# 5_cyber60-smk_periferals.net
KiCad netlist of a schematic drawn in Altium Designer
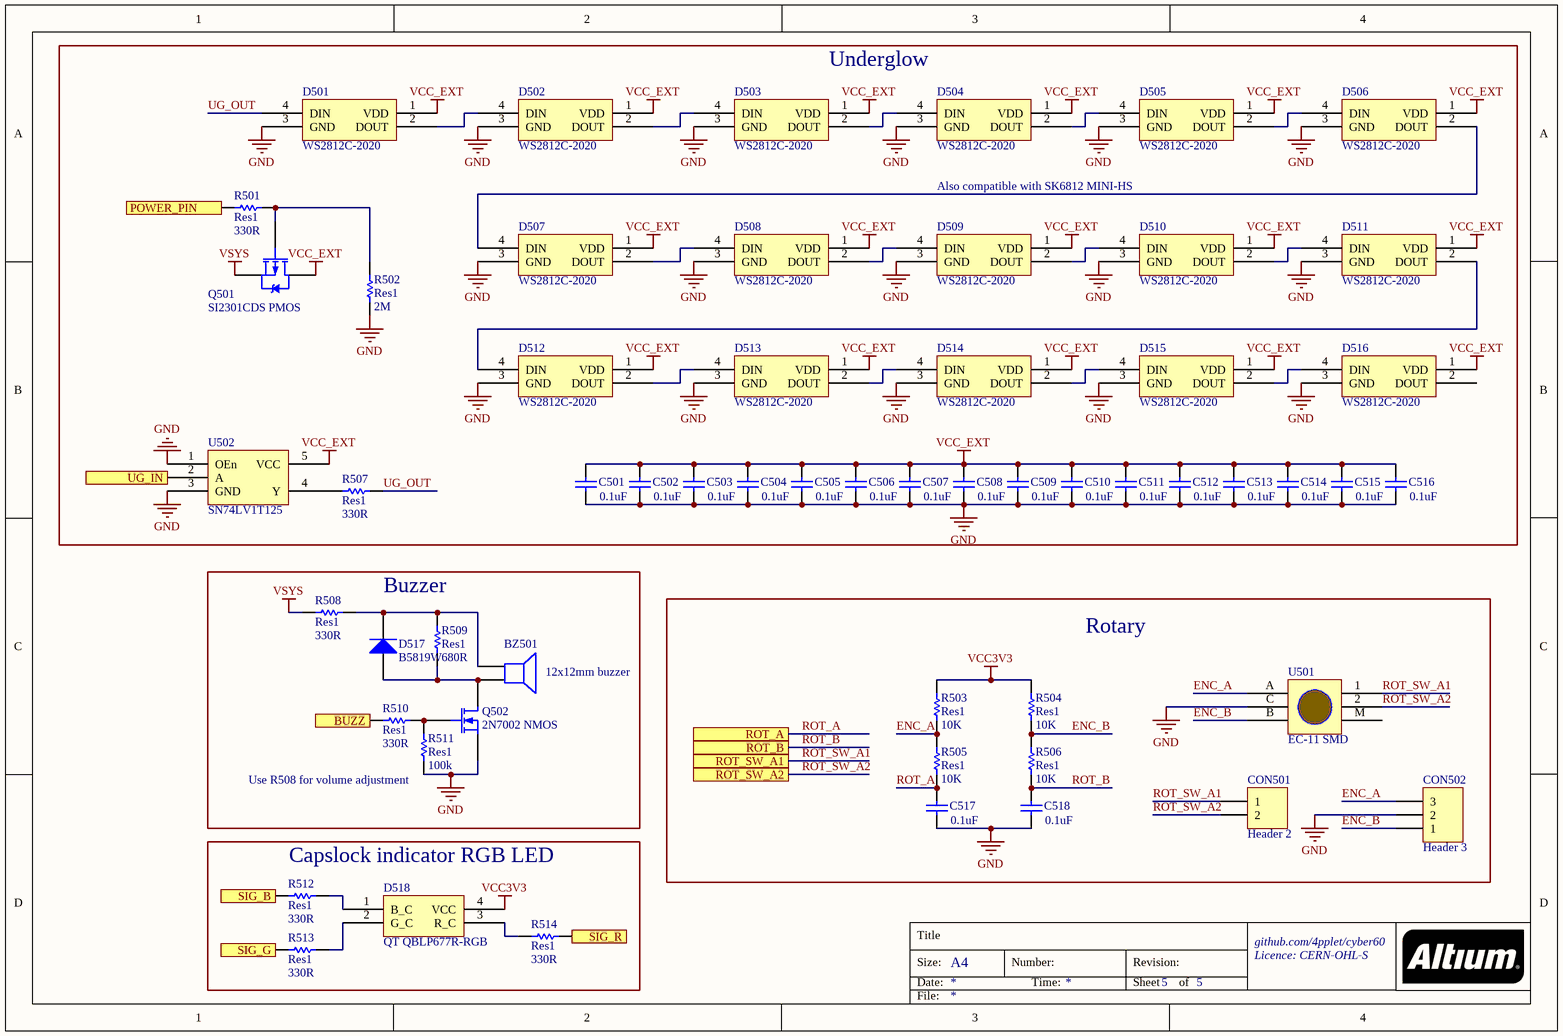
[diagram p0: 5_cyber60-smk_periferals.SchDoc]

(export (version "E")
  (design (tool "Eeschema 10.0.6"))
  (components
    (comp (ref "BZ501")
      (value "12x12mm buzzer")
      (footprint "buzzer 12x12")
      (description "Loudspeaker")
      (fields (field (name "LCSC PART #") "C409829") (field (name "MRF.PART") "YS-SBZ1230"))
      (libsource (lib "Miscellaneous Devices") (part "Speaker"))
    )
    (comp (ref "C501")
      (value "0.1uF")
      (footprint "C0603[1608]")
      (description "Capacitor")
      (fields (field (name "MFG") "KEMET") (field (name "LCSC PART #") "C14663"))
      (libsource (lib "Miscellaneous Devices") (part "Cap"))
    )
    (comp (ref "C502")
      (value "0.1uF")
      (footprint "C0603[1608]")
      (description "Capacitor")
      (fields (field (name "MFG") "KEMET") (field (name "LCSC PART #") "C14663"))
      (libsource (lib "Miscellaneous Devices") (part "Cap"))
    )
    (comp (ref "C503")
      (value "0.1uF")
      (footprint "C0603[1608]")
      (description "Capacitor")
      (fields (field (name "MFG") "KEMET") (field (name "LCSC PART #") "C14663"))
      (libsource (lib "Miscellaneous Devices") (part "Cap"))
    )
    (comp (ref "C504")
      (value "0.1uF")
      (footprint "C0603[1608]")
      (description "Capacitor")
      (fields (field (name "MFG") "KEMET") (field (name "LCSC PART #") "C14663"))
      (libsource (lib "Miscellaneous Devices") (part "Cap"))
    )
    (comp (ref "C505")
      (value "0.1uF")
      (footprint "C0603[1608]")
      (description "Capacitor")
      (fields (field (name "MFG") "KEMET") (field (name "LCSC PART #") "C14663"))
      (libsource (lib "Miscellaneous Devices") (part "Cap"))
    )
    (comp (ref "C506")
      (value "0.1uF")
      (footprint "C0603[1608]")
      (description "Capacitor")
      (fields (field (name "MFG") "KEMET") (field (name "LCSC PART #") "C14663"))
      (libsource (lib "Miscellaneous Devices") (part "Cap"))
    )
    (comp (ref "C507")
      (value "0.1uF")
      (footprint "C0603[1608]")
      (description "Capacitor")
      (fields (field (name "MFG") "KEMET") (field (name "LCSC PART #") "C14663"))
      (libsource (lib "Miscellaneous Devices") (part "Cap"))
    )
    (comp (ref "C508")
      (value "0.1uF")
      (footprint "C0603[1608]")
      (description "Capacitor")
      (fields (field (name "MFG") "KEMET") (field (name "LCSC PART #") "C14663"))
      (libsource (lib "Miscellaneous Devices") (part "Cap"))
    )
    (comp (ref "C509")
      (value "0.1uF")
      (footprint "C0603[1608]")
      (description "Capacitor")
      (fields (field (name "MFG") "KEMET") (field (name "LCSC PART #") "C14663"))
      (libsource (lib "Miscellaneous Devices") (part "Cap"))
    )
    (comp (ref "C510")
      (value "0.1uF")
      (footprint "C0603[1608]")
      (description "Capacitor")
      (fields (field (name "MFG") "KEMET") (field (name "LCSC PART #") "C14663"))
      (libsource (lib "Miscellaneous Devices") (part "Cap"))
    )
    (comp (ref "C511")
      (value "0.1uF")
      (footprint "C0603[1608]")
      (description "Capacitor")
      (fields (field (name "MFG") "KEMET") (field (name "LCSC PART #") "C14663"))
      (libsource (lib "Miscellaneous Devices") (part "Cap"))
    )
    (comp (ref "C512")
      (value "0.1uF")
      (footprint "C0603[1608]")
      (description "Capacitor")
      (fields (field (name "MFG") "KEMET") (field (name "LCSC PART #") "C14663"))
      (libsource (lib "Miscellaneous Devices") (part "Cap"))
    )
    (comp (ref "C513")
      (value "0.1uF")
      (footprint "C0603[1608]")
      (description "Capacitor")
      (fields (field (name "MFG") "KEMET") (field (name "LCSC PART #") "C14663"))
      (libsource (lib "Miscellaneous Devices") (part "Cap"))
    )
    (comp (ref "C514")
      (value "0.1uF")
      (footprint "C0603[1608]")
      (description "Capacitor")
      (fields (field (name "MFG") "KEMET") (field (name "LCSC PART #") "C14663"))
      (libsource (lib "Miscellaneous Devices") (part "Cap"))
    )
    (comp (ref "C515")
      (value "0.1uF")
      (footprint "C0603[1608]")
      (description "Capacitor")
      (fields (field (name "MFG") "KEMET") (field (name "LCSC PART #") "C14663"))
      (libsource (lib "Miscellaneous Devices") (part "Cap"))
    )
    (comp (ref "C516")
      (value "0.1uF")
      (footprint "C0603[1608]")
      (description "Capacitor")
      (fields (field (name "MFG") "KEMET") (field (name "LCSC PART #") "C14663"))
      (libsource (lib "Miscellaneous Devices") (part "Cap"))
    )
    (comp (ref "C517")
      (value "0.1uF")
      (footprint "C0603[1608]")
      (description "Capacitor")
      (fields (field (name "MFG") "KEMET") (field (name "LCSC PART #") "C14663"))
      (libsource (lib "Miscellaneous Devices") (part "Cap"))
    )
    (comp (ref "C518")
      (value "0.1uF")
      (footprint "C0603[1608]")
      (description "Capacitor")
      (fields (field (name "MFG") "KEMET") (field (name "LCSC PART #") "C14663"))
      (libsource (lib "Miscellaneous Devices") (part "Cap"))
    )
    (comp (ref "CON501")
      (value "Header 2")
      (footprint "HDR1X2")
      (description "Header, 2-Pin")
      (libsource (lib "Miscellaneous Connectors") (part "Header 2"))
    )
    (comp (ref "CON502")
      (value "Header 3")
      (footprint "HDR1X3")
      (description "Header, 3-Pin")
      (libsource (lib "Miscellaneous Connectors") (part "Header 3"))
    )
    (comp (ref "D501")
      (value "WS2812C-2020")
      (footprint "WS2812B - 2020")
      (fields (field (name "LCSC PART #") "C965556"))
      (libsource (lib "Keebs") (part "WS2812B"))
    )
    (comp (ref "D502")
      (value "WS2812C-2020")
      (footprint "WS2812B - 2020")
      (fields (field (name "LCSC PART #") "C965556"))
      (libsource (lib "Keebs") (part "WS2812B"))
    )
    (comp (ref "D503")
      (value "WS2812C-2020")
      (footprint "WS2812B - 2020")
      (fields (field (name "LCSC PART #") "C965556"))
      (libsource (lib "Keebs") (part "WS2812B"))
    )
    (comp (ref "D504")
      (value "WS2812C-2020")
      (footprint "WS2812B - 2020")
      (fields (field (name "LCSC PART #") "C965556"))
      (libsource (lib "Keebs") (part "WS2812B"))
    )
    (comp (ref "D505")
      (value "WS2812C-2020")
      (footprint "WS2812B - 2020")
      (fields (field (name "LCSC PART #") "C965556"))
      (libsource (lib "Keebs") (part "WS2812B"))
    )
    (comp (ref "D506")
      (value "WS2812C-2020")
      (footprint "WS2812B - 2020")
      (fields (field (name "LCSC PART #") "C965556"))
      (libsource (lib "Keebs") (part "WS2812B"))
    )
    (comp (ref "D507")
      (value "WS2812C-2020")
      (footprint "WS2812B - 2020")
      (fields (field (name "LCSC PART #") "C965556"))
      (libsource (lib "Keebs") (part "WS2812B"))
    )
    (comp (ref "D508")
      (value "WS2812C-2020")
      (footprint "WS2812B - 2020")
      (fields (field (name "LCSC PART #") "C965556"))
      (libsource (lib "Keebs") (part "WS2812B"))
    )
    (comp (ref "D509")
      (value "WS2812C-2020")
      (footprint "WS2812B - 2020")
      (fields (field (name "LCSC PART #") "C965556"))
      (libsource (lib "Keebs") (part "WS2812B"))
    )
    (comp (ref "D510")
      (value "WS2812C-2020")
      (footprint "WS2812B - 2020")
      (fields (field (name "LCSC PART #") "C965556"))
      (libsource (lib "Keebs") (part "WS2812B"))
    )
    (comp (ref "D511")
      (value "WS2812C-2020")
      (footprint "WS2812B - 2020")
      (fields (field (name "LCSC PART #") "C965556"))
      (libsource (lib "Keebs") (part "WS2812B"))
    )
    (comp (ref "D512")
      (value "WS2812C-2020")
      (footprint "WS2812B - 2020")
      (fields (field (name "LCSC PART #") "C965556"))
      (libsource (lib "Keebs") (part "WS2812B"))
    )
    (comp (ref "D513")
      (value "WS2812C-2020")
      (footprint "WS2812B - 2020")
      (fields (field (name "LCSC PART #") "C965556"))
      (libsource (lib "Keebs") (part "WS2812B"))
    )
    (comp (ref "D514")
      (value "WS2812C-2020")
      (footprint "WS2812B - 2020")
      (fields (field (name "LCSC PART #") "C965556"))
      (libsource (lib "Keebs") (part "WS2812B"))
    )
    (comp (ref "D515")
      (value "WS2812C-2020")
      (footprint "WS2812B - 2020")
      (fields (field (name "LCSC PART #") "C965556"))
      (libsource (lib "Keebs") (part "WS2812B"))
    )
    (comp (ref "D516")
      (value "WS2812C-2020")
      (footprint "WS2812B - 2020")
      (fields (field (name "LCSC PART #") "C965556"))
      (libsource (lib "Keebs") (part "WS2812B"))
    )
    (comp (ref "D517")
      (value "B5819W")
      (footprint "SOD-123")
      (description "Default Diode")
      (fields (field (name "LCSC PART #") "C8598"))
      (libsource (lib "Miscellaneous Devices") (part "Diode"))
    )
    (comp (ref "D518")
      (value "QT QBLP677R-RGB")
      (footprint "QT QBLP677R-RGB")
      (description "RGB LED")
      (fields (field (name "MFG") "QT Brightek (QTB)"))
      (libsource (lib "Keebs") (part "QT QBLP677R-RGB"))
    )
    (comp (ref "Q501")
      (value "SI2301CDS PMOS")
      (footprint "SOT-23-3")
      (description "P-Channel Power MOSFET")
      (fields (field (name "MRF.PART") "SI2301CDS-T1-GE3") (field (name "LCSC PART #") "C10487"))
      (libsource (lib "Miscellaneous Devices") (part "PMOS-2"))
    )
    (comp (ref "Q502")
      (value "2N7002 NMOS")
      (footprint "SOT-23-3")
      (description "N-Channel MOSFET")
      (fields (field (name "LCSC PART #") "C8545") (field (name "MRF.PART") "2N7002"))
      (libsource (lib "Miscellaneous Devices") (part "MOSFET-N"))
    )
    (comp (ref "R501")
      (value "Res1")
      (footprint "R0603[1608]")
      (description "Resistor")
      (fields
        (field (name "ALTIUM_VALUE") "330R")
        (field (name "LCSC PART #") "C23138")
        (field (name "MRF.PART") "0603WAF3300T5E")
      )
      (libsource (lib "Miscellaneous Devices") (part "Res1"))
    )
    (comp (ref "R502")
      (value "Res1")
      (footprint "R0603[1608]")
      (description "Resistor")
      (fields
        (field (name "ALTIUM_VALUE") "2M")
        (field (name "MRF.PART") "0603WAF2004T5E")
        (field (name "LCSC PART #") "C22976")
      )
      (libsource (lib "Miscellaneous Devices") (part "Res1"))
    )
    (comp (ref "R503")
      (value "Res1")
      (footprint "R0603[1608]")
      (description "Resistor")
      (fields
        (field (name "ALTIUM_VALUE") "10K")
        (field (name "MRF.PART") "0603WAF1002T5E")
        (field (name "LCSC PART #") "C25804")
      )
      (libsource (lib "Miscellaneous Devices") (part "Res1"))
    )
    (comp (ref "R504")
      (value "Res1")
      (footprint "R0603[1608]")
      (description "Resistor")
      (fields
        (field (name "ALTIUM_VALUE") "10K")
        (field (name "MRF.PART") "0603WAF1002T5E")
        (field (name "LCSC PART #") "C25804")
      )
      (libsource (lib "Miscellaneous Devices") (part "Res1"))
    )
    (comp (ref "R505")
      (value "Res1")
      (footprint "R0603[1608]")
      (description "Resistor")
      (fields
        (field (name "ALTIUM_VALUE") "10K")
        (field (name "MRF.PART") "0603WAF1002T5E")
        (field (name "LCSC PART #") "C25804")
      )
      (libsource (lib "Miscellaneous Devices") (part "Res1"))
    )
    (comp (ref "R506")
      (value "Res1")
      (footprint "R0603[1608]")
      (description "Resistor")
      (fields
        (field (name "ALTIUM_VALUE") "10K")
        (field (name "MRF.PART") "0603WAF1002T5E")
        (field (name "LCSC PART #") "C25804")
      )
      (libsource (lib "Miscellaneous Devices") (part "Res1"))
    )
    (comp (ref "R507")
      (value "Res1")
      (footprint "R0603[1608]")
      (description "Resistor")
      (fields
        (field (name "ALTIUM_VALUE") "330R")
        (field (name "LCSC PART #") "C23138")
        (field (name "MRF.PART") "0603WAF3300T5E")
      )
      (libsource (lib "Miscellaneous Devices") (part "Res1"))
    )
    (comp (ref "R508")
      (value "Res1")
      (footprint "R0603[1608]")
      (description "Resistor")
      (fields
        (field (name "ALTIUM_VALUE") "330R")
        (field (name "LCSC PART #") "C23138")
        (field (name "MRF.PART") "0603WAF3300T5E")
      )
      (libsource (lib "Miscellaneous Devices") (part "Res1"))
    )
    (comp (ref "R509")
      (value "Res1")
      (footprint "R0603[1608]")
      (description "Resistor")
      (fields
        (field (name "ALTIUM_VALUE") "680R")
        (field (name "MRF.PART") "0603WAF6800T5E")
        (field (name "LCSC PART #") "C23228")
      )
      (libsource (lib "Miscellaneous Devices") (part "Res1"))
    )
    (comp (ref "R510")
      (value "Res1")
      (footprint "R0603[1608]")
      (description "Resistor")
      (fields
        (field (name "ALTIUM_VALUE") "330R")
        (field (name "LCSC PART #") "C23138")
        (field (name "MRF.PART") "0603WAF3300T5E")
      )
      (libsource (lib "Miscellaneous Devices") (part "Res1"))
    )
    (comp (ref "R511")
      (value "Res1")
      (footprint "R0603[1608]")
      (description "Resistor")
      (fields
        (field (name "ALTIUM_VALUE") "100k")
        (field (name "MRF.PART") "0603WAF1003T5E")
        (field (name "LCSC PART #") "C25803")
      )
      (libsource (lib "Miscellaneous Devices") (part "Res1"))
    )
    (comp (ref "R512")
      (value "Res1")
      (footprint "R0603[1608]")
      (description "Resistor")
      (fields
        (field (name "ALTIUM_VALUE") "330R")
        (field (name "LCSC PART #") "C23138")
        (field (name "MRF.PART") "0603WAF3300T5E")
      )
      (libsource (lib "Miscellaneous Devices") (part "Res1"))
    )
    (comp (ref "R513")
      (value "Res1")
      (footprint "R0603[1608]")
      (description "Resistor")
      (fields
        (field (name "ALTIUM_VALUE") "330R")
        (field (name "LCSC PART #") "C23138")
        (field (name "MRF.PART") "0603WAF3300T5E")
      )
      (libsource (lib "Miscellaneous Devices") (part "Res1"))
    )
    (comp (ref "R514")
      (value "Res1")
      (footprint "R0603[1608]")
      (description "Resistor")
      (fields
        (field (name "ALTIUM_VALUE") "330R")
        (field (name "LCSC PART #") "C23138")
        (field (name "MRF.PART") "0603WAF3300T5E")
      )
      (libsource (lib "Miscellaneous Devices") (part "Res1"))
    )
    (comp (ref "U501") (value "EC-11 SMD") (footprint "EC11-SMD") (libsource (lib "Keebs") (part "EC-11")))
    (comp (ref "U502")
      (value "SN74LV1T125")
      (footprint "SOT-23-5")
      (description "SN74LV1T125 or SN74LV1T34. Connect OE to GND")
      (fields (field (name "LCSC PART #") "C473338") (field (name "MRF.PART") "SN74LV1T125DBVR"))
      (libsource (lib "Keebs") (part "SN74LV1T125"))
    )
  )
  (nets
    (net (code "1") (name "/BUZZ") (class "Default")
      (node (ref "R510") (pin "2") (pinfunction "2_2") (pintype "passive"))
    )
    (net (code "2") (name "/ENC_A") (class "Default")
      (node (ref "CON502") (pin "3") (pinfunction "3_3") (pintype "passive"))
      (node (ref "R503") (pin "2") (pinfunction "2_2") (pintype "passive"))
      (node (ref "R505") (pin "1") (pinfunction "1_1") (pintype "passive"))
      (node (ref "U501") (pin "A") (pinfunction "B_A") (pintype "passive"))
    )
    (net (code "3") (name "/ENC_B") (class "Default")
      (node (ref "CON502") (pin "1") (pinfunction "1_1") (pintype "passive"))
      (node (ref "R504") (pin "2") (pinfunction "2_2") (pintype "passive"))
      (node (ref "R506") (pin "1") (pinfunction "1_1") (pintype "passive"))
      (node (ref "U501") (pin "B") (pinfunction "B_B") (pintype "passive"))
    )
    (net (code "4") (name "/POWER_PIN") (class "Default")
      (node (ref "R501") (pin "1") (pinfunction "1_1") (pintype "passive"))
    )
    (net (code "5") (name "/ROT_A") (class "Default")
      (node (ref "C517") (pin "2") (pinfunction "2_2") (pintype "passive"))
      (node (ref "R505") (pin "2") (pinfunction "2_2") (pintype "passive"))
    )
    (net (code "6") (name "/ROT_B") (class "Default")
      (node (ref "C518") (pin "2") (pinfunction "2_2") (pintype "passive"))
      (node (ref "R506") (pin "2") (pinfunction "2_2") (pintype "passive"))
    )
    (net (code "7") (name "/ROT_SW_A1") (class "Default")
      (node (ref "CON501") (pin "1") (pinfunction "1_1") (pintype "passive"))
      (node (ref "U501") (pin "1") (pinfunction "1_1") (pintype "passive"))
    )
    (net (code "8") (name "/ROT_SW_A2") (class "Default")
      (node (ref "CON501") (pin "2") (pinfunction "2_2") (pintype "passive"))
      (node (ref "U501") (pin "2") (pinfunction "2_2") (pintype "passive"))
    )
    (net (code "9") (name "/SIG_B") (class "Default")
      (node (ref "R512") (pin "2") (pinfunction "2_2") (pintype "passive"))
    )
    (net (code "10") (name "/SIG_G") (class "Default")
      (node (ref "R513") (pin "2") (pinfunction "2_2") (pintype "passive"))
    )
    (net (code "11") (name "/SIG_R") (class "Default")
      (node (ref "R514") (pin "1") (pinfunction "1_1") (pintype "passive"))
    )
    (net (code "12") (name "/UG_IN") (class "Default")
      (node (ref "U502") (pin "2") (pinfunction "A_2") (pintype "passive"))
    )
    (net (code "13") (name "/UG_OUT") (class "Default")
      (node (ref "D501") (pin "4") (pinfunction "DIN_4") (pintype "passive"))
      (node (ref "R507") (pin "1") (pinfunction "1_1") (pintype "passive"))
    )
    (net (code "14") (name "GND") (class "Default")
      (node (ref "C501") (pin "1") (pinfunction "1_1") (pintype "passive"))
      (node (ref "C502") (pin "1") (pinfunction "1_1") (pintype "passive"))
      (node (ref "C503") (pin "1") (pinfunction "1_1") (pintype "passive"))
      (node (ref "C504") (pin "1") (pinfunction "1_1") (pintype "passive"))
      (node (ref "C505") (pin "1") (pinfunction "1_1") (pintype "passive"))
      (node (ref "C506") (pin "1") (pinfunction "1_1") (pintype "passive"))
      (node (ref "C507") (pin "1") (pinfunction "1_1") (pintype "passive"))
      (node (ref "C508") (pin "1") (pinfunction "1_1") (pintype "passive"))
      (node (ref "C509") (pin "1") (pinfunction "1_1") (pintype "passive"))
      (node (ref "C510") (pin "1") (pinfunction "1_1") (pintype "passive"))
      (node (ref "C511") (pin "1") (pinfunction "1_1") (pintype "passive"))
      (node (ref "C512") (pin "1") (pinfunction "1_1") (pintype "passive"))
      (node (ref "C513") (pin "1") (pinfunction "1_1") (pintype "passive"))
      (node (ref "C514") (pin "1") (pinfunction "1_1") (pintype "passive"))
      (node (ref "C515") (pin "1") (pinfunction "1_1") (pintype "passive"))
      (node (ref "C516") (pin "1") (pinfunction "1_1") (pintype "passive"))
      (node (ref "C517") (pin "1") (pinfunction "1_1") (pintype "passive"))
      (node (ref "C518") (pin "1") (pinfunction "1_1") (pintype "passive"))
      (node (ref "CON502") (pin "2") (pinfunction "2_2") (pintype "passive"))
      (node (ref "D501") (pin "3") (pinfunction "GND_3") (pintype "passive"))
      (node (ref "D502") (pin "3") (pinfunction "GND_3") (pintype "passive"))
      (node (ref "D503") (pin "3") (pinfunction "GND_3") (pintype "passive"))
      (node (ref "D504") (pin "3") (pinfunction "GND_3") (pintype "passive"))
      (node (ref "D505") (pin "3") (pinfunction "GND_3") (pintype "passive"))
      (node (ref "D506") (pin "3") (pinfunction "GND_3") (pintype "passive"))
      (node (ref "D507") (pin "3") (pinfunction "GND_3") (pintype "passive"))
      (node (ref "D508") (pin "3") (pinfunction "GND_3") (pintype "passive"))
      (node (ref "D509") (pin "3") (pinfunction "GND_3") (pintype "passive"))
      (node (ref "D510") (pin "3") (pinfunction "GND_3") (pintype "passive"))
      (node (ref "D511") (pin "3") (pinfunction "GND_3") (pintype "passive"))
      (node (ref "D512") (pin "3") (pinfunction "GND_3") (pintype "passive"))
      (node (ref "D513") (pin "3") (pinfunction "GND_3") (pintype "passive"))
      (node (ref "D514") (pin "3") (pinfunction "GND_3") (pintype "passive"))
      (node (ref "D515") (pin "3") (pinfunction "GND_3") (pintype "passive"))
      (node (ref "D516") (pin "3") (pinfunction "GND_3") (pintype "passive"))
      (node (ref "Q502") (pin "2") (pinfunction "S_2") (pintype "passive"))
      (node (ref "R502") (pin "1") (pinfunction "1_1") (pintype "passive"))
      (node (ref "R511") (pin "2") (pinfunction "2_2") (pintype "passive"))
      (node (ref "U501") (pin "C") (pinfunction "C_C") (pintype "passive"))
      (node (ref "U502") (pin "1") (pinfunction "OEn_1") (pintype "passive"))
      (node (ref "U502") (pin "3") (pinfunction "GND_3") (pintype "passive"))
    )
    (net (code "15") (name "Net-(D501-DOUT)") (class "Default")
      (node (ref "D501") (pin "2") (pinfunction "DOUT_2") (pintype "passive"))
      (node (ref "D502") (pin "4") (pinfunction "DIN_4") (pintype "passive"))
    )
    (net (code "16") (name "Net-(D502-DOUT)") (class "Default")
      (node (ref "D502") (pin "2") (pinfunction "DOUT_2") (pintype "passive"))
      (node (ref "D503") (pin "4") (pinfunction "DIN_4") (pintype "passive"))
    )
    (net (code "17") (name "Net-(D503-DOUT)") (class "Default")
      (node (ref "D503") (pin "2") (pinfunction "DOUT_2") (pintype "passive"))
      (node (ref "D504") (pin "4") (pinfunction "DIN_4") (pintype "passive"))
    )
    (net (code "18") (name "Net-(D504-DOUT)") (class "Default")
      (node (ref "D504") (pin "2") (pinfunction "DOUT_2") (pintype "passive"))
      (node (ref "D505") (pin "4") (pinfunction "DIN_4") (pintype "passive"))
    )
    (net (code "19") (name "Net-(D505-DOUT)") (class "Default")
      (node (ref "D505") (pin "2") (pinfunction "DOUT_2") (pintype "passive"))
      (node (ref "D506") (pin "4") (pinfunction "DIN_4") (pintype "passive"))
    )
    (net (code "20") (name "Net-(D506-DOUT)") (class "Default")
      (node (ref "D506") (pin "2") (pinfunction "DOUT_2") (pintype "passive"))
      (node (ref "D507") (pin "4") (pinfunction "DIN_4") (pintype "passive"))
    )
    (net (code "21") (name "Net-(D507-DOUT)") (class "Default")
      (node (ref "D507") (pin "2") (pinfunction "DOUT_2") (pintype "passive"))
      (node (ref "D508") (pin "4") (pinfunction "DIN_4") (pintype "passive"))
    )
    (net (code "22") (name "Net-(D508-DOUT)") (class "Default")
      (node (ref "D508") (pin "2") (pinfunction "DOUT_2") (pintype "passive"))
      (node (ref "D509") (pin "4") (pinfunction "DIN_4") (pintype "passive"))
    )
    (net (code "23") (name "Net-(D509-DOUT)") (class "Default")
      (node (ref "D509") (pin "2") (pinfunction "DOUT_2") (pintype "passive"))
      (node (ref "D510") (pin "4") (pinfunction "DIN_4") (pintype "passive"))
    )
    (net (code "24") (name "Net-(D510-DOUT)") (class "Default")
      (node (ref "D510") (pin "2") (pinfunction "DOUT_2") (pintype "passive"))
      (node (ref "D511") (pin "4") (pinfunction "DIN_4") (pintype "passive"))
    )
    (net (code "25") (name "Net-(D511-DOUT)") (class "Default")
      (node (ref "D511") (pin "2") (pinfunction "DOUT_2") (pintype "passive"))
      (node (ref "D512") (pin "4") (pinfunction "DIN_4") (pintype "passive"))
    )
    (net (code "26") (name "Net-(D512-DOUT)") (class "Default")
      (node (ref "D512") (pin "2") (pinfunction "DOUT_2") (pintype "passive"))
      (node (ref "D513") (pin "4") (pinfunction "DIN_4") (pintype "passive"))
    )
    (net (code "27") (name "Net-(D513-DOUT)") (class "Default")
      (node (ref "D513") (pin "2") (pinfunction "DOUT_2") (pintype "passive"))
      (node (ref "D514") (pin "4") (pinfunction "DIN_4") (pintype "passive"))
    )
    (net (code "28") (name "Net-(D514-DOUT)") (class "Default")
      (node (ref "D514") (pin "2") (pinfunction "DOUT_2") (pintype "passive"))
      (node (ref "D515") (pin "4") (pinfunction "DIN_4") (pintype "passive"))
    )
    (net (code "29") (name "Net-(D515-DOUT)") (class "Default")
      (node (ref "D515") (pin "2") (pinfunction "DOUT_2") (pintype "passive"))
      (node (ref "D516") (pin "4") (pinfunction "DIN_4") (pintype "passive"))
    )
    (net (code "30") (name "Net-(D517-A)") (class "Default")
      (node (ref "BZ501") (pin "2") (pinfunction "2_2") (pintype "passive"))
      (node (ref "D517") (pin "1") (pinfunction "A_1") (pintype "passive"))
      (node (ref "Q502") (pin "3") (pinfunction "D_3") (pintype "passive"))
      (node (ref "R509") (pin "2") (pinfunction "2_2") (pintype "passive"))
    )
    (net (code "31") (name "Net-(D517-K)") (class "Default")
      (node (ref "BZ501") (pin "1") (pinfunction "1_1") (pintype "passive"))
      (node (ref "D517") (pin "2") (pinfunction "K_2") (pintype "passive"))
      (node (ref "R508") (pin "1") (pinfunction "1_1") (pintype "passive"))
      (node (ref "R509") (pin "1") (pinfunction "1_1") (pintype "passive"))
    )
    (net (code "32") (name "Net-(D518-B_C)") (class "Default")
      (node (ref "D518") (pin "1") (pinfunction "B_C_1") (pintype "passive"))
      (node (ref "R512") (pin "1") (pinfunction "1_1") (pintype "passive"))
    )
    (net (code "33") (name "Net-(D518-G_C)") (class "Default")
      (node (ref "D518") (pin "2") (pinfunction "G_C_2") (pintype "passive"))
      (node (ref "R513") (pin "1") (pinfunction "1_1") (pintype "passive"))
    )
    (net (code "34") (name "Net-(D518-R_C)") (class "Default")
      (node (ref "D518") (pin "3") (pinfunction "R_C_3") (pintype "passive"))
      (node (ref "R514") (pin "2") (pinfunction "2_2") (pintype "passive"))
    )
    (net (code "35") (name "Net-(Q501-G)") (class "Default")
      (node (ref "Q501") (pin "1") (pinfunction "G_1") (pintype "passive"))
      (node (ref "R501") (pin "2") (pinfunction "2_2") (pintype "passive"))
      (node (ref "R502") (pin "2") (pinfunction "2_2") (pintype "passive"))
    )
    (net (code "36") (name "Net-(Q502-G)") (class "Default")
      (node (ref "Q502") (pin "1") (pinfunction "G_1") (pintype "passive"))
      (node (ref "R510") (pin "1") (pinfunction "1_1") (pintype "passive"))
      (node (ref "R511") (pin "1") (pinfunction "1_1") (pintype "passive"))
    )
    (net (code "37") (name "Net-(U502-Y)") (class "Default")
      (node (ref "R507") (pin "2") (pinfunction "2_2") (pintype "passive"))
      (node (ref "U502") (pin "4") (pinfunction "Y_4") (pintype "passive"))
    )
    (net (code "38") (name "VCC3V3") (class "Default")
      (node (ref "D518") (pin "4") (pinfunction "VCC_4") (pintype "passive"))
      (node (ref "R503") (pin "1") (pinfunction "1_1") (pintype "passive"))
      (node (ref "R504") (pin "1") (pinfunction "1_1") (pintype "passive"))
    )
    (net (code "39") (name "VCC_EXT") (class "Default")
      (node (ref "C501") (pin "2") (pinfunction "2_2") (pintype "passive"))
      (node (ref "C502") (pin "2") (pinfunction "2_2") (pintype "passive"))
      (node (ref "C503") (pin "2") (pinfunction "2_2") (pintype "passive"))
      (node (ref "C504") (pin "2") (pinfunction "2_2") (pintype "passive"))
      (node (ref "C505") (pin "2") (pinfunction "2_2") (pintype "passive"))
      (node (ref "C506") (pin "2") (pinfunction "2_2") (pintype "passive"))
      (node (ref "C507") (pin "2") (pinfunction "2_2") (pintype "passive"))
      (node (ref "C508") (pin "2") (pinfunction "2_2") (pintype "passive"))
      (node (ref "C509") (pin "2") (pinfunction "2_2") (pintype "passive"))
      (node (ref "C510") (pin "2") (pinfunction "2_2") (pintype "passive"))
      (node (ref "C511") (pin "2") (pinfunction "2_2") (pintype "passive"))
      (node (ref "C512") (pin "2") (pinfunction "2_2") (pintype "passive"))
      (node (ref "C513") (pin "2") (pinfunction "2_2") (pintype "passive"))
      (node (ref "C514") (pin "2") (pinfunction "2_2") (pintype "passive"))
      (node (ref "C515") (pin "2") (pinfunction "2_2") (pintype "passive"))
      (node (ref "C516") (pin "2") (pinfunction "2_2") (pintype "passive"))
      (node (ref "D501") (pin "1") (pinfunction "VDD_1") (pintype "passive"))
      (node (ref "D502") (pin "1") (pinfunction "VDD_1") (pintype "passive"))
      (node (ref "D503") (pin "1") (pinfunction "VDD_1") (pintype "passive"))
      (node (ref "D504") (pin "1") (pinfunction "VDD_1") (pintype "passive"))
      (node (ref "D505") (pin "1") (pinfunction "VDD_1") (pintype "passive"))
      (node (ref "D506") (pin "1") (pinfunction "VDD_1") (pintype "passive"))
      (node (ref "D507") (pin "1") (pinfunction "VDD_1") (pintype "passive"))
      (node (ref "D508") (pin "1") (pinfunction "VDD_1") (pintype "passive"))
      (node (ref "D509") (pin "1") (pinfunction "VDD_1") (pintype "passive"))
      (node (ref "D510") (pin "1") (pinfunction "VDD_1") (pintype "passive"))
      (node (ref "D511") (pin "1") (pinfunction "VDD_1") (pintype "passive"))
      (node (ref "D512") (pin "1") (pinfunction "VDD_1") (pintype "passive"))
      (node (ref "D513") (pin "1") (pinfunction "VDD_1") (pintype "passive"))
      (node (ref "D514") (pin "1") (pinfunction "VDD_1") (pintype "passive"))
      (node (ref "D515") (pin "1") (pinfunction "VDD_1") (pintype "passive"))
      (node (ref "D516") (pin "1") (pinfunction "VDD_1") (pintype "passive"))
      (node (ref "Q501") (pin "3") (pinfunction "D_3") (pintype "passive"))
      (node (ref "U502") (pin "5") (pinfunction "VCC_5") (pintype "passive"))
    )
    (net (code "40") (name "VSYS") (class "Default")
      (node (ref "Q501") (pin "2") (pinfunction "S_2") (pintype "passive"))
      (node (ref "R508") (pin "2") (pinfunction "2_2") (pintype "passive"))
    )
    (net (code "41") (name "unconnected-(D516-DOUT-Pad2)") (class "Default")
      (node (ref "D516") (pin "2") (pinfunction "DOUT_2") (pintype "passive"))
    )
    (net (code "42") (name "unconnected-(U501-PadM)") (class "Default")
      (node (ref "U501") (pin "M") (pinfunction "M_M") (pintype "passive"))
    )
  )
)
